# RH021_1.net
KiCad netlist of a schematic drawn in EAGLE
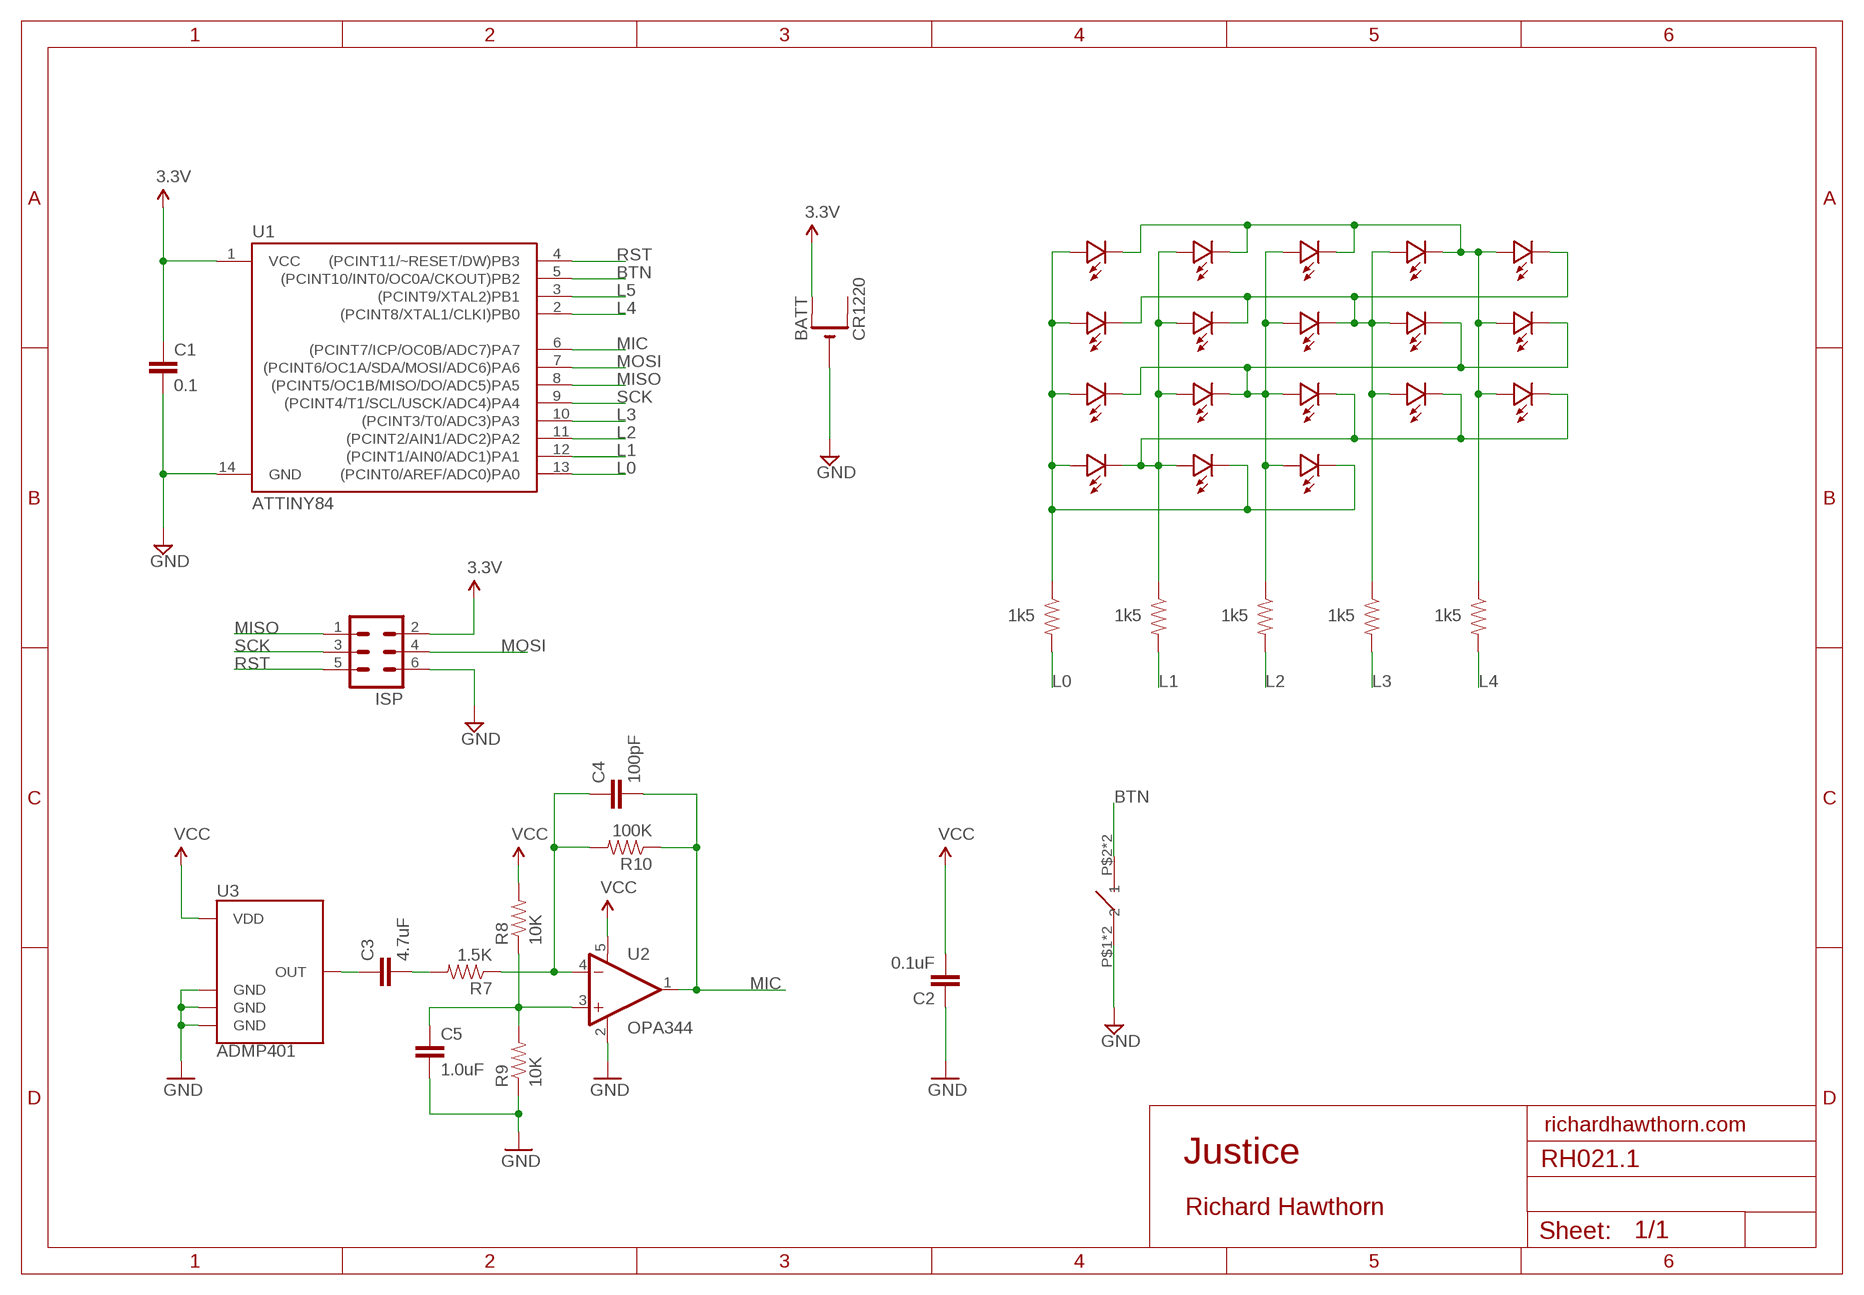
[diagram p0: schematic, sheet 1]

(export (version "E")
  (design (tool "Eeschema 10.0.6"))
  (components
    (comp (ref "BATT")
      (value "CR1220")
      (footprint "eagle-import:CR1220-SMD")
      (libsource (lib "eagle-import") (part "CR1220SMT"))
    )
    (comp (ref "BTN1")
      (value "TURTLE-3PIN")
      (footprint "eagle-import:TURTLE-3PIN")
      (libsource (lib "eagle-import") (part "TURTLE-3PIN"))
    )
    (comp (ref "C1")
      (value "0.1")
      (footprint "eagle-import:0603-CAP")
      (libsource (lib "eagle-import") (part "CAP0603-CAP"))
    )
    (comp (ref "C2")
      (value "0.1uF")
      (footprint "eagle-import:0402-CAP")
      (libsource (lib "eagle-import") (part "SparkFun_CAP0402-CAP"))
    )
    (comp (ref "C3")
      (value "4.7uF")
      (footprint "eagle-import:0402-CAP")
      (libsource (lib "eagle-import") (part "SparkFun_CAP0402-CAP"))
    )
    (comp (ref "C4")
      (value "100pF")
      (footprint "eagle-import:0402-CAP")
      (libsource (lib "eagle-import") (part "SparkFun_CAP0402-CAP"))
    )
    (comp (ref "C5")
      (value "1.0uF")
      (footprint "eagle-import:0402-CAP")
      (libsource (lib "eagle-import") (part "SparkFun_CAP0402-CAP"))
    )
    (comp (ref "ISP")
      (value "MA03-2")
      (footprint "eagle-import:MA03-2")
      (libsource (lib "eagle-import") (part "MA03-2"))
    )
    (comp (ref "LED1")
      (value "LED0603")
      (footprint "eagle-import:0603-LED")
      (libsource (lib "eagle-import") (part "LED0603"))
    )
    (comp (ref "LED2")
      (value "LED0603")
      (footprint "eagle-import:0603-LED")
      (libsource (lib "eagle-import") (part "LED0603"))
    )
    (comp (ref "LED3")
      (value "LED0603")
      (footprint "eagle-import:0603-LED")
      (libsource (lib "eagle-import") (part "LED0603"))
    )
    (comp (ref "LED4")
      (value "LED0603")
      (footprint "eagle-import:0603-LED")
      (libsource (lib "eagle-import") (part "LED0603"))
    )
    (comp (ref "LED5")
      (value "LED0603")
      (footprint "eagle-import:0603-LED")
      (libsource (lib "eagle-import") (part "LED0603"))
    )
    (comp (ref "LED6")
      (value "LED0603")
      (footprint "eagle-import:0603-LED")
      (libsource (lib "eagle-import") (part "LED0603"))
    )
    (comp (ref "LED7")
      (value "LED0603")
      (footprint "eagle-import:0603-LED")
      (libsource (lib "eagle-import") (part "LED0603"))
    )
    (comp (ref "LED8")
      (value "LED0603")
      (footprint "eagle-import:0603-LED")
      (libsource (lib "eagle-import") (part "LED0603"))
    )
    (comp (ref "LED9")
      (value "LED0603")
      (footprint "eagle-import:0603-LED")
      (libsource (lib "eagle-import") (part "LED0603"))
    )
    (comp (ref "LED10")
      (value "LED0603")
      (footprint "eagle-import:0603-LED")
      (libsource (lib "eagle-import") (part "LED0603"))
    )
    (comp (ref "LED11")
      (value "LED0603")
      (footprint "eagle-import:0603-LED")
      (libsource (lib "eagle-import") (part "LED0603"))
    )
    (comp (ref "LED12")
      (value "LED0603")
      (footprint "eagle-import:0603-LED")
      (libsource (lib "eagle-import") (part "LED0603"))
    )
    (comp (ref "LED13")
      (value "LED0603")
      (footprint "eagle-import:0603-LED")
      (libsource (lib "eagle-import") (part "LED0603"))
    )
    (comp (ref "LED14")
      (value "LED0603")
      (footprint "eagle-import:0603-LED")
      (libsource (lib "eagle-import") (part "LED0603"))
    )
    (comp (ref "LED15")
      (value "LED0603")
      (footprint "eagle-import:0603-LED")
      (libsource (lib "eagle-import") (part "LED0603"))
    )
    (comp (ref "LED16")
      (value "LED0603")
      (footprint "eagle-import:0603-LED")
      (libsource (lib "eagle-import") (part "LED0603"))
    )
    (comp (ref "LED17")
      (value "LED0603")
      (footprint "eagle-import:0603-LED")
      (libsource (lib "eagle-import") (part "LED0603"))
    )
    (comp (ref "LED18")
      (value "LED0603")
      (footprint "eagle-import:0603-LED")
      (libsource (lib "eagle-import") (part "LED0603"))
    )
    (comp (ref "R1")
      (value "1k5")
      (footprint "eagle-import:0603-RES")
      (libsource (lib "eagle-import") (part "RESISTOR0603-RES"))
    )
    (comp (ref "R2")
      (value "1k5")
      (footprint "eagle-import:0603-RES")
      (libsource (lib "eagle-import") (part "RESISTOR0603-RES"))
    )
    (comp (ref "R3")
      (value "1k5")
      (footprint "eagle-import:0603-RES")
      (libsource (lib "eagle-import") (part "RESISTOR0603-RES"))
    )
    (comp (ref "R4")
      (value "1k5")
      (footprint "eagle-import:0603-RES")
      (libsource (lib "eagle-import") (part "RESISTOR0603-RES"))
    )
    (comp (ref "R5")
      (value "1k5")
      (footprint "eagle-import:0603-RES")
      (libsource (lib "eagle-import") (part "RESISTOR0603-RES"))
    )
    (comp (ref "R7")
      (value "1.5K")
      (footprint "eagle-import:0402-RES")
      (libsource (lib "eagle-import") (part "SparkFun_RESISTOR0402-RES"))
    )
    (comp (ref "R8")
      (value "10K")
      (footprint "eagle-import:0402-RES")
      (libsource (lib "eagle-import") (part "SparkFun_RESISTOR0402-RES"))
    )
    (comp (ref "R9")
      (value "10K")
      (footprint "eagle-import:0402-RES")
      (libsource (lib "eagle-import") (part "SparkFun_RESISTOR0402-RES"))
    )
    (comp (ref "R10")
      (value "100K")
      (footprint "eagle-import:0402-RES")
      (libsource (lib "eagle-import") (part "SparkFun_RESISTOR0402-RES"))
    )
    (comp (ref "U1")
      (value "ATTINY84")
      (footprint "eagle-import:SO14")
      (libsource (lib "eagle-import") (part "ATTINY84"))
    )
    (comp (ref "U2")
      (value "OPA344")
      (footprint "eagle-import:SOT23-5")
      (libsource (lib "eagle-import") (part "OPA344"))
    )
    (comp (ref "U3")
      (value "ADMP401")
      (footprint "eagle-import:ADMP401")
      (libsource (lib "eagle-import") (part "ADMP401"))
    )
  )
  (nets
    (net (code "1") (name "/BTN") (class "Default")
      (node (ref "BTN1") (pin "P$2") (pinfunction "2_P$2") (pintype "bidirectional"))
      (node (ref "BTN1") (pin "P$4") (pinfunction "2_P$4") (pintype "bidirectional"))
      (node (ref "U1") (pin "5") (pinfunction "(PCINT10/INT0/OC0A/CKOUT)PB2_5") (pintype "bidirectional"))
    )
    (net (code "2") (name "/L0") (class "Default")
      (node (ref "R1") (pin "2") (pinfunction "2_2") (pintype "passive"))
      (node (ref "U1") (pin "13") (pinfunction "(PCINT0/AREF/ADC0)PA0_13") (pintype "bidirectional"))
    )
    (net (code "3") (name "/L1") (class "Default")
      (node (ref "R2") (pin "2") (pinfunction "2_2") (pintype "passive"))
      (node (ref "U1") (pin "12") (pinfunction "(PCINT1/AIN0/ADC1)PA1_12") (pintype "bidirectional"))
    )
    (net (code "4") (name "/L2") (class "Default")
      (node (ref "R3") (pin "2") (pinfunction "2_2") (pintype "passive"))
      (node (ref "U1") (pin "11") (pinfunction "(PCINT2/AIN1/ADC2)PA2_11") (pintype "bidirectional"))
    )
    (net (code "5") (name "/L3") (class "Default")
      (node (ref "R4") (pin "2") (pinfunction "2_2") (pintype "passive"))
      (node (ref "U1") (pin "10") (pinfunction "(PCINT3/T0/ADC3)PA3_10") (pintype "bidirectional"))
    )
    (net (code "6") (name "/L4") (class "Default")
      (node (ref "R5") (pin "2") (pinfunction "2_2") (pintype "passive"))
      (node (ref "U1") (pin "2") (pinfunction "(PCINT8/XTAL1/CLKI)PB0_2") (pintype "bidirectional"))
    )
    (net (code "7") (name "/L5") (class "Default")
      (node (ref "U1") (pin "3") (pinfunction "(PCINT9/XTAL2)PB1_3") (pintype "bidirectional"))
    )
    (net (code "8") (name "/MIC") (class "Default")
      (node (ref "C4") (pin "2") (pinfunction "2_2") (pintype "passive"))
      (node (ref "R10") (pin "1") (pinfunction "1_1") (pintype "passive"))
      (node (ref "U1") (pin "6") (pinfunction "(PCINT7/ICP/OC0B/ADC7)PA7_6") (pintype "bidirectional"))
      (node (ref "U2") (pin "1") (pinfunction "OUT_1") (pintype "output"))
    )
    (net (code "9") (name "/MISO") (class "Default")
      (node (ref "ISP") (pin "1") (pinfunction "1_1") (pintype "passive"))
      (node (ref "U1") (pin "8") (pinfunction "(PCINT5/OC1B/MISO/DO/ADC5)PA5_8") (pintype "bidirectional"))
    )
    (net (code "10") (name "/MOSI") (class "Default")
      (node (ref "ISP") (pin "4") (pinfunction "4_4") (pintype "passive"))
      (node (ref "U1") (pin "7") (pinfunction "(PCINT6/OC1A/SDA/MOSI/ADC6)PA6_7") (pintype "bidirectional"))
    )
    (net (code "11") (name "/RST") (class "Default")
      (node (ref "ISP") (pin "5") (pinfunction "5_5") (pintype "passive"))
      (node (ref "U1") (pin "4") (pinfunction "(PCINT11/~{RESET/DW})PB3_4") (pintype "bidirectional"))
    )
    (net (code "12") (name "/SCK") (class "Default")
      (node (ref "ISP") (pin "3") (pinfunction "3_3") (pintype "passive"))
      (node (ref "U1") (pin "9") (pinfunction "(PCINT4/T1/SCL/USCK/ADC4)PA4_9") (pintype "bidirectional"))
    )
    (net (code "13") (name "3.3V") (class "Default")
      (node (ref "BATT") (pin "+$1") (pinfunction "+_+$1") (pintype "passive"))
      (node (ref "C1") (pin "1") (pinfunction "1_1") (pintype "passive"))
      (node (ref "C2") (pin "2") (pinfunction "2_2") (pintype "passive"))
      (node (ref "ISP") (pin "2") (pinfunction "2_2") (pintype "passive"))
      (node (ref "R8") (pin "2") (pinfunction "2_2") (pintype "passive"))
      (node (ref "U1") (pin "1") (pinfunction "VCC_1") (pintype "bidirectional"))
      (node (ref "U2") (pin "5") (pinfunction "V+_5") (pintype "power_in"))
      (node (ref "U3") (pin "5") (pinfunction "VDD_5") (pintype "bidirectional"))
    )
    (net (code "14") (name "GND") (class "Default")
      (node (ref "BATT") (pin "-") (pinfunction "-_-") (pintype "passive"))
      (node (ref "BTN1") (pin "P$1") (pinfunction "1_P$1") (pintype "bidirectional"))
      (node (ref "BTN1") (pin "P$3") (pinfunction "1_P$3") (pintype "bidirectional"))
      (node (ref "C1") (pin "2") (pinfunction "2_2") (pintype "passive"))
      (node (ref "C2") (pin "1") (pinfunction "1_1") (pintype "passive"))
      (node (ref "C5") (pin "2") (pinfunction "2_2") (pintype "passive"))
      (node (ref "ISP") (pin "6") (pinfunction "6_6") (pintype "passive"))
      (node (ref "R9") (pin "1") (pinfunction "1_1") (pintype "passive"))
      (node (ref "U1") (pin "14") (pinfunction "GND_14") (pintype "bidirectional"))
      (node (ref "U2") (pin "2") (pinfunction "V-_2") (pintype "power_in"))
      (node (ref "U3") (pin "2") (pinfunction "GND_2") (pintype "bidirectional"))
      (node (ref "U3") (pin "4") (pinfunction "GND_4") (pintype "bidirectional"))
      (node (ref "U3") (pin "6") (pinfunction "GND_6") (pintype "bidirectional"))
    )
    (net (code "15") (name "Net-(C3-Pad2)") (class "Default")
      (node (ref "C3") (pin "2") (pinfunction "2_2") (pintype "passive"))
      (node (ref "R7") (pin "2") (pinfunction "2_2") (pintype "passive"))
    )
    (net (code "16") (name "Net-(LED1-PadMINUS)") (class "Default")
      (node (ref "LED1") (pin "MINUS") (pinfunction "MINUS_MINUS") (pintype "passive"))
      (node (ref "LED10") (pin "PLUS") (pinfunction "PLUS_PLUS") (pintype "passive"))
      (node (ref "LED15") (pin "PLUS") (pinfunction "PLUS_PLUS") (pintype "passive"))
      (node (ref "LED2") (pin "MINUS") (pinfunction "MINUS_MINUS") (pintype "passive"))
      (node (ref "LED3") (pin "MINUS") (pinfunction "MINUS_MINUS") (pintype "passive"))
      (node (ref "LED4") (pin "MINUS") (pinfunction "MINUS_MINUS") (pintype "passive"))
      (node (ref "LED5") (pin "PLUS") (pinfunction "PLUS_PLUS") (pintype "passive"))
      (node (ref "R5") (pin "1") (pinfunction "1_1") (pintype "passive"))
    )
    (net (code "17") (name "Net-(LED1-PadPLUS)") (class "Default")
      (node (ref "LED1") (pin "PLUS") (pinfunction "PLUS_PLUS") (pintype "passive"))
      (node (ref "LED11") (pin "PLUS") (pinfunction "PLUS_PLUS") (pintype "passive"))
      (node (ref "LED16") (pin "PLUS") (pinfunction "PLUS_PLUS") (pintype "passive"))
      (node (ref "LED17") (pin "MINUS") (pinfunction "MINUS_MINUS") (pintype "passive"))
      (node (ref "LED18") (pin "MINUS") (pinfunction "MINUS_MINUS") (pintype "passive"))
      (node (ref "LED6") (pin "PLUS") (pinfunction "PLUS_PLUS") (pintype "passive"))
      (node (ref "R1") (pin "1") (pinfunction "1_1") (pintype "passive"))
    )
    (net (code "18") (name "Net-(LED10-PadMINUS)") (class "Default")
      (node (ref "LED10") (pin "MINUS") (pinfunction "MINUS_MINUS") (pintype "passive"))
      (node (ref "LED11") (pin "MINUS") (pinfunction "MINUS_MINUS") (pintype "passive"))
      (node (ref "LED12") (pin "MINUS") (pinfunction "MINUS_MINUS") (pintype "passive"))
      (node (ref "LED13") (pin "PLUS") (pinfunction "PLUS_PLUS") (pintype "passive"))
      (node (ref "LED18") (pin "PLUS") (pinfunction "PLUS_PLUS") (pintype "passive"))
      (node (ref "LED3") (pin "PLUS") (pinfunction "PLUS_PLUS") (pintype "passive"))
      (node (ref "LED8") (pin "PLUS") (pinfunction "PLUS_PLUS") (pintype "passive"))
      (node (ref "LED9") (pin "MINUS") (pinfunction "MINUS_MINUS") (pintype "passive"))
      (node (ref "R3") (pin "1") (pinfunction "1_1") (pintype "passive"))
    )
    (net (code "19") (name "Net-(LED12-PadPLUS)") (class "Default")
      (node (ref "LED12") (pin "PLUS") (pinfunction "PLUS_PLUS") (pintype "passive"))
      (node (ref "LED13") (pin "MINUS") (pinfunction "MINUS_MINUS") (pintype "passive"))
      (node (ref "LED14") (pin "MINUS") (pinfunction "MINUS_MINUS") (pintype "passive"))
      (node (ref "LED15") (pin "MINUS") (pinfunction "MINUS_MINUS") (pintype "passive"))
      (node (ref "LED16") (pin "MINUS") (pinfunction "MINUS_MINUS") (pintype "passive"))
      (node (ref "LED17") (pin "PLUS") (pinfunction "PLUS_PLUS") (pintype "passive"))
      (node (ref "LED2") (pin "PLUS") (pinfunction "PLUS_PLUS") (pintype "passive"))
      (node (ref "LED7") (pin "PLUS") (pinfunction "PLUS_PLUS") (pintype "passive"))
      (node (ref "R2") (pin "1") (pinfunction "1_1") (pintype "passive"))
    )
    (net (code "20") (name "Net-(LED14-PadPLUS)") (class "Default")
      (node (ref "LED14") (pin "PLUS") (pinfunction "PLUS_PLUS") (pintype "passive"))
      (node (ref "LED4") (pin "PLUS") (pinfunction "PLUS_PLUS") (pintype "passive"))
      (node (ref "LED5") (pin "MINUS") (pinfunction "MINUS_MINUS") (pintype "passive"))
      (node (ref "LED6") (pin "MINUS") (pinfunction "MINUS_MINUS") (pintype "passive"))
      (node (ref "LED7") (pin "MINUS") (pinfunction "MINUS_MINUS") (pintype "passive"))
      (node (ref "LED8") (pin "MINUS") (pinfunction "MINUS_MINUS") (pintype "passive"))
      (node (ref "LED9") (pin "PLUS") (pinfunction "PLUS_PLUS") (pintype "passive"))
      (node (ref "R4") (pin "1") (pinfunction "1_1") (pintype "passive"))
    )
    (net (code "21") (name "Net-(U2-+IN)") (class "Default")
      (node (ref "C5") (pin "1") (pinfunction "1_1") (pintype "passive"))
      (node (ref "R8") (pin "1") (pinfunction "1_1") (pintype "passive"))
      (node (ref "R9") (pin "2") (pinfunction "2_2") (pintype "passive"))
      (node (ref "U2") (pin "3") (pinfunction "+IN_3") (pintype "input"))
    )
    (net (code "22") (name "Net-(U2--IN)") (class "Default")
      (node (ref "C4") (pin "1") (pinfunction "1_1") (pintype "passive"))
      (node (ref "R10") (pin "2") (pinfunction "2_2") (pintype "passive"))
      (node (ref "R7") (pin "1") (pinfunction "1_1") (pintype "passive"))
      (node (ref "U2") (pin "4") (pinfunction "-IN_4") (pintype "input"))
    )
    (net (code "23") (name "Net-(U3-OUT)") (class "Default")
      (node (ref "C3") (pin "1") (pinfunction "1_1") (pintype "passive"))
      (node (ref "U3") (pin "1") (pinfunction "OUT_1") (pintype "bidirectional"))
    )
    (net (code "24") (name "unconnected-(BATT-+1-Pad+$2)") (class "Default")
      (node (ref "BATT") (pin "+$2") (pinfunction "+1_+$2") (pintype "passive"))
    )
  )
)
